# Moo_AFE.net
KiCad netlist of a schematic drawn in Altium Designer
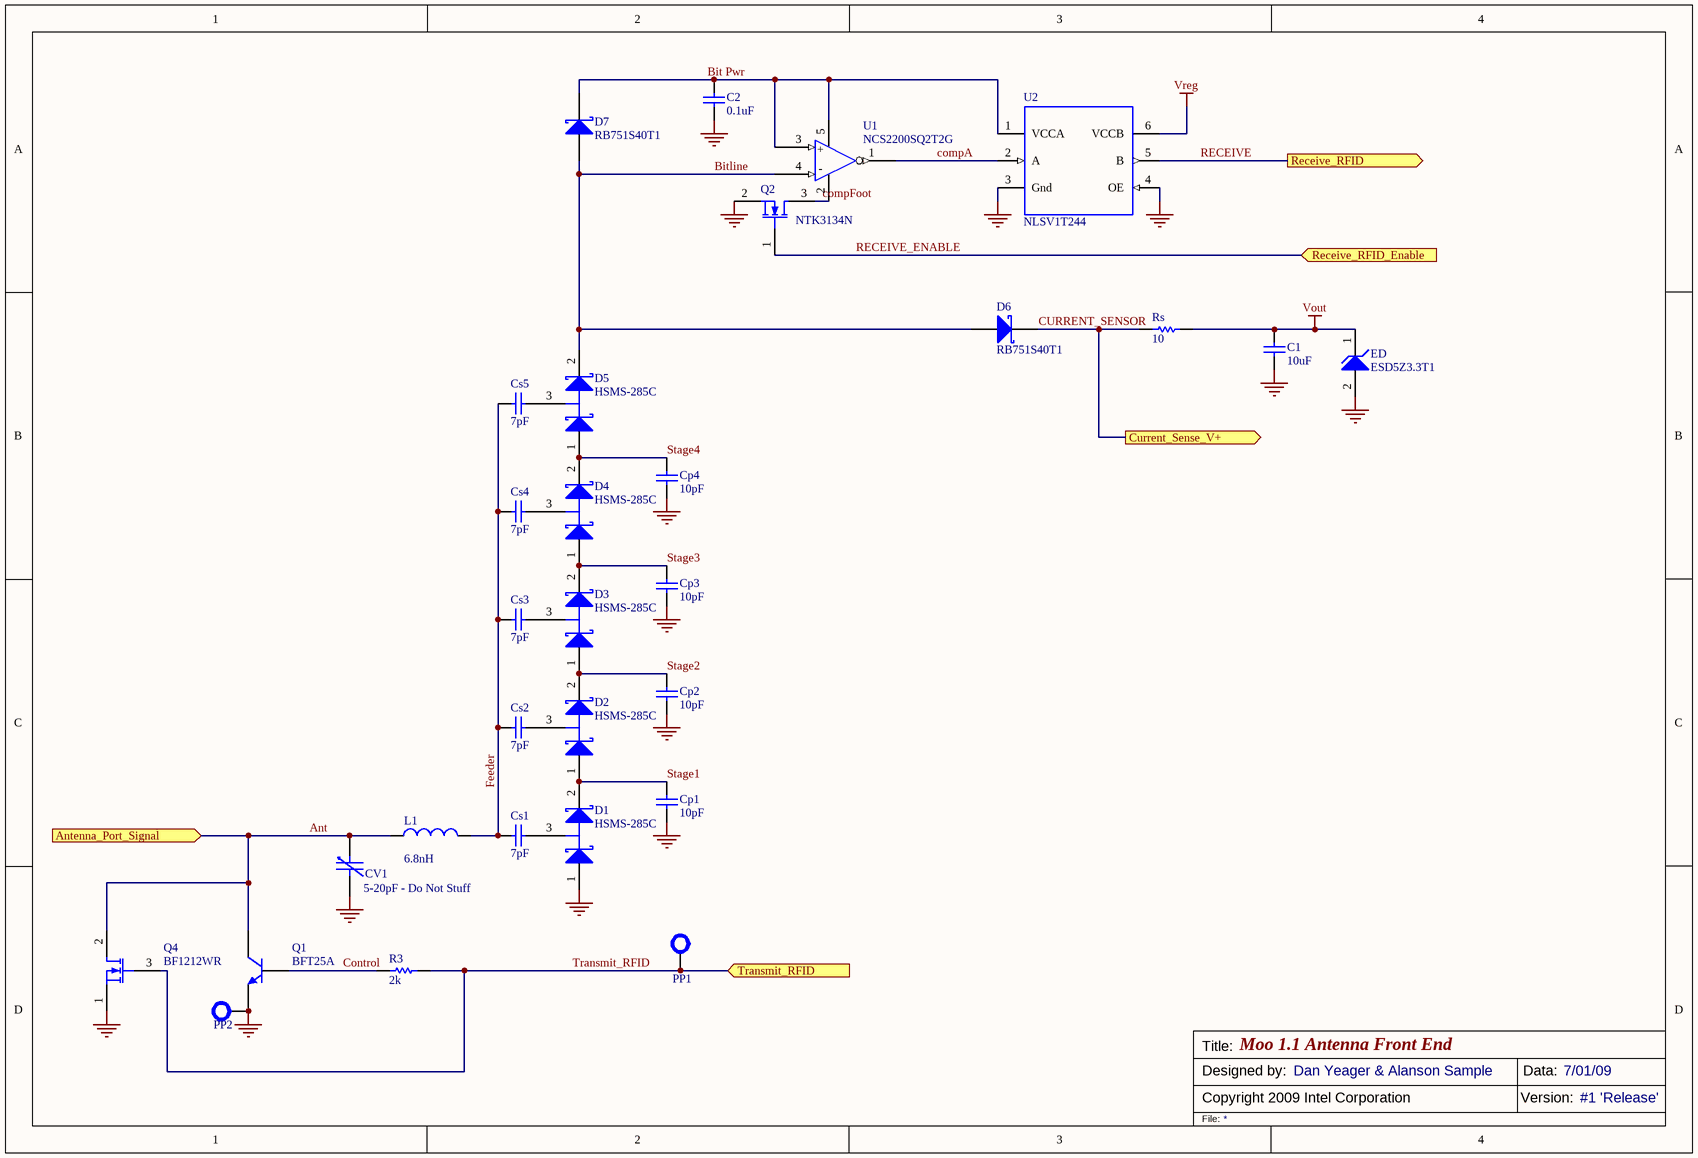
[diagram p0: Moo_AFE.SchDoc]

(export (version "E")
  (design (tool "Eeschema 10.0.6"))
  (components
    (comp (ref "C1")
      (value "10uF")
      (footprint "0805")
      (description "Ceramic Capacitor - Standard")
      (fields (field (name "Comment") "Ceramic_Chip_Capacitor"))
      (libsource (lib "WispLib") (part "Ceramic_Chip_Capacitor"))
    )
    (comp (ref "C2")
      (value "0.1uF")
      (footprint "WispLib:0402")
      (description "Ceramic Capacitor - Standard")
      (fields (field (name "Comment") "Ceramic_Chip_Capacitor"))
      (libsource (lib "WispLib") (part "Ceramic_Chip_Capacitor"))
    )
    (comp (ref "Cp1")
      (value "10pF")
      (footprint "WispLib:0402")
      (description "Ceramic Capacitor - Standard")
      (fields (field (name "Comment") "Ceramic_Chip_Capacitor"))
      (libsource (lib "WispLib") (part "Ceramic_Chip_Capacitor"))
    )
    (comp (ref "Cp2")
      (value "10pF")
      (footprint "WispLib:0402")
      (description "Ceramic Capacitor - Standard")
      (fields (field (name "Comment") "Ceramic_Chip_Capacitor"))
      (libsource (lib "WispLib") (part "Ceramic_Chip_Capacitor"))
    )
    (comp (ref "Cp3")
      (value "10pF")
      (footprint "WispLib:0402")
      (description "Ceramic Capacitor - Standard")
      (fields (field (name "Comment") "Ceramic_Chip_Capacitor"))
      (libsource (lib "WispLib") (part "Ceramic_Chip_Capacitor"))
    )
    (comp (ref "Cp4")
      (value "10pF")
      (footprint "WispLib:0402")
      (description "Ceramic Capacitor - Standard")
      (fields (field (name "Comment") "Ceramic_Chip_Capacitor"))
      (libsource (lib "WispLib") (part "Ceramic_Chip_Capacitor"))
    )
    (comp (ref "Cs1")
      (value "7pF")
      (footprint "WispLib:0402")
      (description "Ceramic Capacitor - Standard")
      (fields (field (name "Comment") "Ceramic_Chip_Capacitor"))
      (libsource (lib "WispLib") (part "Ceramic_Chip_Capacitor"))
    )
    (comp (ref "Cs2")
      (value "7pF")
      (footprint "WispLib:0402")
      (description "Ceramic Capacitor - Standard")
      (fields (field (name "Comment") "Ceramic_Chip_Capacitor"))
      (libsource (lib "WispLib") (part "Ceramic_Chip_Capacitor"))
    )
    (comp (ref "Cs3")
      (value "7pF")
      (footprint "WispLib:0402")
      (description "Ceramic Capacitor - Standard")
      (fields (field (name "Comment") "Ceramic_Chip_Capacitor"))
      (libsource (lib "WispLib") (part "Ceramic_Chip_Capacitor"))
    )
    (comp (ref "Cs4")
      (value "7pF")
      (footprint "WispLib:0402")
      (description "Ceramic Capacitor - Standard")
      (fields (field (name "Comment") "Ceramic_Chip_Capacitor"))
      (libsource (lib "WispLib") (part "Ceramic_Chip_Capacitor"))
    )
    (comp (ref "Cs5")
      (value "7pF")
      (footprint "WispLib:0402")
      (description "Ceramic Capacitor - Standard")
      (fields (field (name "Comment") "Ceramic_Chip_Capacitor"))
      (libsource (lib "WispLib") (part "Ceramic_Chip_Capacitor"))
    )
    (comp (ref "CV1")
      (value "5-20pF - Do Not Stuff")
      (footprint "WispLib:Var-Cap_603")
      (description "Var-Cap 603 Compatible, DK: 490-2009 & SG2026CT")
      (fields (field (name "Comment") "Var Cap"))
      (libsource (lib "*") (part "Var-Cap/603"))
    )
    (comp (ref "D1")
      (value "HSMS-285C")
      (footprint "WispLib:SOT-323, HSMS-285C")
      (description "Agilent Schottky Diode, Bridge Quad, HSMS-285C")
      (libsource (lib "WispLib") (part "HSMS-285C"))
    )
    (comp (ref "D2")
      (value "HSMS-285C")
      (footprint "WispLib:SOT-323, HSMS-285C")
      (description "Agilent Schottky Diode, Bridge Quad, HSMS-285C")
      (libsource (lib "WispLib") (part "HSMS-285C"))
    )
    (comp (ref "D3")
      (value "HSMS-285C")
      (footprint "WispLib:SOT-323, HSMS-285C")
      (description "Agilent Schottky Diode, Bridge Quad, HSMS-285C")
      (libsource (lib "WispLib") (part "HSMS-285C"))
    )
    (comp (ref "D4")
      (value "HSMS-285C")
      (footprint "WispLib:SOT-323, HSMS-285C")
      (description "Agilent Schottky Diode, Bridge Quad, HSMS-285C")
      (libsource (lib "WispLib") (part "HSMS-285C"))
    )
    (comp (ref "D5")
      (value "HSMS-285C")
      (footprint "WispLib:SOT-323, HSMS-285C")
      (description "Agilent Schottky Diode, Bridge Quad, HSMS-285C")
      (libsource (lib "WispLib") (part "HSMS-285C"))
    )
    (comp (ref "D6")
      (value "RB751S40T1")
      (footprint "WispLib:SOD-523")
      (description "Schottky Diode")
      (fields (field (name "PUBLISHER") "Altium Limited"))
      (libsource (lib "WispLib") (part "RB751S40T1"))
    )
    (comp (ref "D7")
      (value "RB751S40T1")
      (footprint "WispLib:SOD-523")
      (description "Schottky Diode")
      (fields (field (name "PUBLISHER") "Altium Limited"))
      (libsource (lib "*") (part "Schottky Diode"))
    )
    (comp (ref "ED")
      (value "ESD5Z3.3T1")
      (footprint "WispLib:SOD-523")
      (description "5V Overvoltage Protection Zener")
      (libsource (lib "*") (part "ESD5Z3.3T1"))
    )
    (comp (ref "L1")
      (value "6.8nH")
      (footprint "WispLib:0603")
      (description "Inductor")
      (libsource (lib "*") (part "Inductor"))
    )
    (comp (ref "PP1")
      (value "Probe Point")
      (footprint "Probe Point")
      (description "Probe Point for debug")
      (libsource (lib "WispLib") (part "Probe Point"))
    )
    (comp (ref "PP2")
      (value "Probe Point")
      (footprint "Probe Point")
      (description "Probe Point for debug")
      (libsource (lib "WispLib") (part "Probe Point"))
    )
    (comp (ref "Q1")
      (value "BFT25A")
      (footprint "WispLib:SOT-23")
      (description "NPN 5 GHz Wideband Transistor")
      (libsource (lib "*") (part "BFT25A"))
    )
    (comp (ref "Q2")
      (value "NTK3134N")
      (footprint "SOT723")
      (description "Powe Mosfet 20V, 890mA, Single N-channel")
      (libsource (lib "WispLib") (part "NTK3134N"))
    )
    (comp (ref "Q4") (value "BF1212WR") (footprint "sot343r") (libsource (lib "WispLib") (part "BF1212")))
    (comp (ref "R3")
      (value "2k")
      (footprint "WispLib:0402")
      (description "Thick Film Chip Resistor")
      (libsource (lib "*") (part "Thick Film Chip Resistor"))
    )
    (comp (ref "Rs")
      (value "10")
      (footprint "WispLib:0402")
      (description "Thick Film Chip Resistor")
      (libsource (lib "*") (part "Thick Film Chip Resistor"))
    )
    (comp (ref "U1")
      (value "NCS2200SQ2T2G")
      (footprint "sc70-5")
      (description "On Semi 10uA Comparator")
      (libsource (lib "WispLib") (part "NCS2200SQ2T2G"))
    )
    (comp (ref "U2")
      (value "NLSV1T244")
      (footprint "UDFN6")
      (description "Level Shifter: 1-Bit Dual-Supply Non-Inverting Level Translator")
      (fields (field (name "PART NUMBER") "ADG3301"))
      (libsource (lib "WispLib") (part "NLSV1T244"))
    )
  )
  (nets
    (net (code "1") (name "/Ant") (class "Default")
      (node (ref "CV1") (pin "1") (pinfunction "1_1") (pintype "passive"))
      (node (ref "L1") (pin "1") (pinfunction "1_1") (pintype "passive"))
      (node (ref "Q1") (pin "3") (pinfunction "C_3") (pintype "passive"))
      (node (ref "Q4") (pin "2") (pinfunction "D_2") (pintype "passive"))
    )
    (net (code "2") (name "/Bit Pwr") (class "Default")
      (node (ref "C2") (pin "1") (pinfunction "1_1") (pintype "passive"))
      (node (ref "D7") (pin "1") (pinfunction "K_1") (pintype "passive"))
      (node (ref "U1") (pin "3") (pinfunction "IN+_3") (pintype "input"))
      (node (ref "U1") (pin "5") (pinfunction "VDD_5") (pintype "power_in"))
      (node (ref "U2") (pin "1") (pinfunction "VCCA_1") (pintype "power_in"))
    )
    (net (code "3") (name "/Bitline") (class "Default")
      (node (ref "D5") (pin "2") (pinfunction "K_2") (pintype "passive"))
      (node (ref "D6") (pin "2") (pinfunction "A_2") (pintype "passive"))
      (node (ref "D7") (pin "2") (pinfunction "A_2") (pintype "passive"))
      (node (ref "U1") (pin "4") (pinfunction "In-_4") (pintype "input"))
    )
    (net (code "4") (name "/CURRENT_SENSOR") (class "Default")
      (node (ref "D6") (pin "1") (pinfunction "C_1") (pintype "passive"))
      (node (ref "Rs") (pin "2") (pinfunction "2_2") (pintype "passive"))
    )
    (net (code "5") (name "/Control") (class "Default")
      (node (ref "Q1") (pin "1") (pinfunction "B_1") (pintype "passive"))
      (node (ref "R3") (pin "1") (pinfunction "1_1") (pintype "passive"))
    )
    (net (code "6") (name "/Feeder") (class "Default")
      (node (ref "Cs1") (pin "1") (pinfunction "1_1") (pintype "passive"))
      (node (ref "Cs2") (pin "1") (pinfunction "1_1") (pintype "passive"))
      (node (ref "Cs3") (pin "1") (pinfunction "1_1") (pintype "passive"))
      (node (ref "Cs4") (pin "1") (pinfunction "1_1") (pintype "passive"))
      (node (ref "Cs5") (pin "1") (pinfunction "1_1") (pintype "passive"))
      (node (ref "L1") (pin "2") (pinfunction "2_2") (pintype "passive"))
    )
    (net (code "7") (name "/RECEIVE") (class "Default")
      (node (ref "U2") (pin "5") (pinfunction "B_5") (pintype "output"))
    )
    (net (code "8") (name "/RECEIVE_ENABLE") (class "Default")
      (node (ref "Q2") (pin "1") (pinfunction "G_1") (pintype "passive"))
    )
    (net (code "9") (name "/Stage1") (class "Default")
      (node (ref "Cp1") (pin "1") (pinfunction "1_1") (pintype "passive"))
      (node (ref "D1") (pin "2") (pinfunction "K_2") (pintype "passive"))
      (node (ref "D2") (pin "1") (pinfunction "A_1") (pintype "passive"))
    )
    (net (code "10") (name "/Stage2") (class "Default")
      (node (ref "Cp2") (pin "1") (pinfunction "1_1") (pintype "passive"))
      (node (ref "D2") (pin "2") (pinfunction "K_2") (pintype "passive"))
      (node (ref "D3") (pin "1") (pinfunction "A_1") (pintype "passive"))
    )
    (net (code "11") (name "/Stage3") (class "Default")
      (node (ref "Cp3") (pin "1") (pinfunction "1_1") (pintype "passive"))
      (node (ref "D3") (pin "2") (pinfunction "K_2") (pintype "passive"))
      (node (ref "D4") (pin "1") (pinfunction "A_1") (pintype "passive"))
    )
    (net (code "12") (name "/Stage4") (class "Default")
      (node (ref "Cp4") (pin "1") (pinfunction "1_1") (pintype "passive"))
      (node (ref "D4") (pin "2") (pinfunction "K_2") (pintype "passive"))
      (node (ref "D5") (pin "1") (pinfunction "A_1") (pintype "passive"))
    )
    (net (code "13") (name "/Transmit_RFID") (class "Default")
      (node (ref "PP1") (pin "0") (pinfunction "0_0") (pintype "passive"))
      (node (ref "Q4") (pin "3") (pinfunction "G_3") (pintype "passive"))
      (node (ref "R3") (pin "2") (pinfunction "2_2") (pintype "passive"))
    )
    (net (code "14") (name "/compA") (class "Default")
      (node (ref "U1") (pin "1") (pinfunction "OUT_1") (pintype "output"))
      (node (ref "U2") (pin "2") (pinfunction "A_2") (pintype "input"))
    )
    (net (code "15") (name "/compFoot") (class "Default")
      (node (ref "Q2") (pin "3") (pinfunction "D_3") (pintype "passive"))
      (node (ref "U1") (pin "2") (pinfunction "Gnd_2") (pintype "power_in"))
    )
    (net (code "16") (name "GND") (class "Default")
      (node (ref "C1") (pin "1") (pinfunction "1_1") (pintype "passive"))
      (node (ref "C2") (pin "2") (pinfunction "2_2") (pintype "passive"))
      (node (ref "CV1") (pin "2") (pinfunction "2_2") (pintype "passive"))
      (node (ref "Cp1") (pin "2") (pinfunction "2_2") (pintype "passive"))
      (node (ref "Cp2") (pin "2") (pinfunction "2_2") (pintype "passive"))
      (node (ref "Cp3") (pin "2") (pinfunction "2_2") (pintype "passive"))
      (node (ref "Cp4") (pin "2") (pinfunction "2_2") (pintype "passive"))
      (node (ref "D1") (pin "1") (pinfunction "A_1") (pintype "passive"))
      (node (ref "ED") (pin "2") (pinfunction "2_2") (pintype "passive"))
      (node (ref "PP2") (pin "0") (pinfunction "0_0") (pintype "passive"))
      (node (ref "Q1") (pin "2") (pinfunction "E_2") (pintype "passive"))
      (node (ref "Q2") (pin "2") (pinfunction "S_2") (pintype "passive"))
      (node (ref "Q4") (pin "1") (pinfunction "S_1") (pintype "passive"))
      (node (ref "U2") (pin "3") (pinfunction "Gnd_3") (pintype "power_in"))
      (node (ref "U2") (pin "4") (pinfunction "OE_4") (pintype "input"))
    )
    (net (code "17") (name "Net-(D1-C)") (class "Default")
      (node (ref "Cs1") (pin "2") (pinfunction "2_2") (pintype "passive"))
      (node (ref "D1") (pin "3") (pinfunction "C_3") (pintype "passive"))
    )
    (net (code "18") (name "Net-(D2-C)") (class "Default")
      (node (ref "Cs2") (pin "2") (pinfunction "2_2") (pintype "passive"))
      (node (ref "D2") (pin "3") (pinfunction "C_3") (pintype "passive"))
    )
    (net (code "19") (name "Net-(D3-C)") (class "Default")
      (node (ref "Cs3") (pin "2") (pinfunction "2_2") (pintype "passive"))
      (node (ref "D3") (pin "3") (pinfunction "C_3") (pintype "passive"))
    )
    (net (code "20") (name "Net-(D4-C)") (class "Default")
      (node (ref "Cs4") (pin "2") (pinfunction "2_2") (pintype "passive"))
      (node (ref "D4") (pin "3") (pinfunction "C_3") (pintype "passive"))
    )
    (net (code "21") (name "Net-(D5-C)") (class "Default")
      (node (ref "Cs5") (pin "2") (pinfunction "2_2") (pintype "passive"))
      (node (ref "D5") (pin "3") (pinfunction "C_3") (pintype "passive"))
    )
    (net (code "22") (name "Vout") (class "Default")
      (node (ref "C1") (pin "2") (pinfunction "2_2") (pintype "passive"))
      (node (ref "ED") (pin "1") (pinfunction "1_1") (pintype "passive"))
      (node (ref "Rs") (pin "1") (pinfunction "1_1") (pintype "passive"))
    )
    (net (code "23") (name "Vreg") (class "Default")
      (node (ref "U2") (pin "6") (pinfunction "VCCB_6") (pintype "power_in"))
    )
  )
)
